# v4_Schematic.net
KiCad netlist of a schematic drawn in Altium Designer
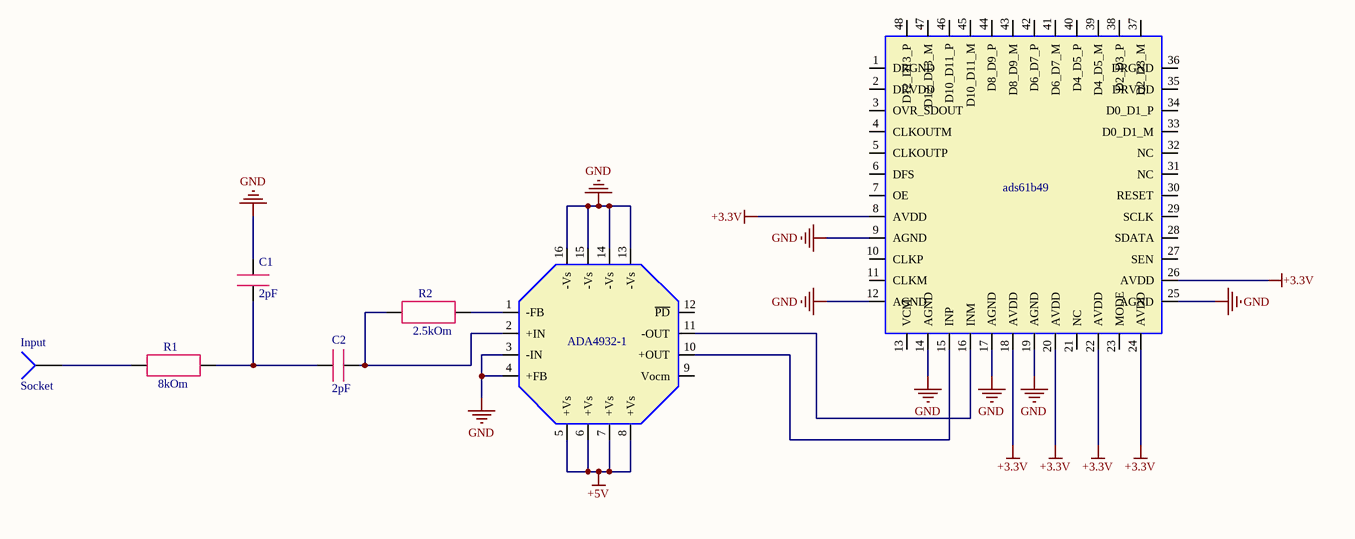
[diagram p0: v4_Schematic.SchDoc]

(export (version "E")
  (design (tool "Eeschema 10.0.6"))
  (components
    (comp (ref "ADA4932-1")
      (value "ADA4932-1")
      (footprint "v4_pcb_librari:ADA4932-1")
      (libsource (lib "v4_librari") (part "ADA4932-1"))
    )
    (comp (ref "ads61b49")
      (value "ads61b49")
      (footprint "v4_pcb_librari:ADS1b49")
      (libsource (lib "v4_librari") (part "ads61b49"))
    )
    (comp (ref "C1")
      (value "2pF")
      (footprint "v4_pcb_librari:C_Capicator")
      (libsource (lib "v4_librari") (part "Ñapacitor"))
    )
    (comp (ref "C2")
      (value "2pF")
      (footprint "v4_pcb_librari:C_Capicator")
      (libsource (lib "v4_librari") (part "Ñapacitor"))
    )
    (comp (ref "Input")
      (value "Socket")
      (footprint "PIN1")
      (fields (field (name "PUBLISHER") "Altium Limited"))
      (libsource (lib "Miscellaneous Connectors") (part "Socket"))
    )
    (comp (ref "R1")
      (value "8kOm")
      (footprint "v4_pcb_librari:R_Resistor")
      (description "8 kOm")
      (libsource (lib "v4_librari") (part "Resistance"))
    )
    (comp (ref "R2")
      (value "2.5kOm")
      (footprint "v4_pcb_librari:R_Resistor")
      (libsource (lib "v4_librari") (part "Resistance"))
    )
  )
  (nets
    (net (code "1") (name "+3.3V") (class "Default")
      (node (ref "ads61b49") (pin "18") (pinfunction "AVDD_18") (pintype "passive"))
      (node (ref "ads61b49") (pin "20") (pinfunction "AVDD_20") (pintype "passive"))
      (node (ref "ads61b49") (pin "22") (pinfunction "AVDD_22") (pintype "passive"))
      (node (ref "ads61b49") (pin "24") (pinfunction "AVDD_24") (pintype "passive"))
      (node (ref "ads61b49") (pin "26") (pinfunction "AVDD_26") (pintype "passive"))
      (node (ref "ads61b49") (pin "8") (pinfunction "AVDD_8") (pintype "passive"))
    )
    (net (code "2") (name "+5V") (class "Default")
      (node (ref "ADA4932-1") (pin "5") (pinfunction "+Vs_5") (pintype "passive"))
      (node (ref "ADA4932-1") (pin "6") (pinfunction "+Vs_6") (pintype "passive"))
      (node (ref "ADA4932-1") (pin "7") (pinfunction "+Vs_7") (pintype "passive"))
      (node (ref "ADA4932-1") (pin "8") (pinfunction "+Vs_8") (pintype "passive"))
    )
    (net (code "3") (name "GND") (class "Default")
      (node (ref "ADA4932-1") (pin "13") (pinfunction "-Vs_13") (pintype "passive"))
      (node (ref "ADA4932-1") (pin "14") (pinfunction "-Vs_14") (pintype "passive"))
      (node (ref "ADA4932-1") (pin "15") (pinfunction "-Vs_15") (pintype "passive"))
      (node (ref "ADA4932-1") (pin "16") (pinfunction "-Vs_16") (pintype "passive"))
      (node (ref "ADA4932-1") (pin "3") (pinfunction "-IN_3") (pintype "passive"))
      (node (ref "ADA4932-1") (pin "4") (pinfunction "+FB_4") (pintype "passive"))
      (node (ref "C1") (pin "2") (pinfunction "2_2") (pintype "passive"))
      (node (ref "ads61b49") (pin "12") (pinfunction "AGND_12") (pintype "passive"))
      (node (ref "ads61b49") (pin "14") (pinfunction "AGND_14") (pintype "passive"))
      (node (ref "ads61b49") (pin "17") (pinfunction "AGND_17") (pintype "passive"))
      (node (ref "ads61b49") (pin "19") (pinfunction "AGND_19") (pintype "passive"))
      (node (ref "ads61b49") (pin "25") (pinfunction "AGND_25") (pintype "passive"))
      (node (ref "ads61b49") (pin "9") (pinfunction "AGND_9") (pintype "passive"))
    )
    (net (code "4") (name "Net-(ADA4932-1-+IN)") (class "Default")
      (node (ref "ADA4932-1") (pin "2") (pinfunction "+IN_2") (pintype "passive"))
      (node (ref "C2") (pin "2") (pinfunction "2_2") (pintype "passive"))
      (node (ref "R2") (pin "1") (pinfunction "1_1") (pintype "passive"))
    )
    (net (code "5") (name "Net-(ADA4932-1-+OUT)") (class "Default")
      (node (ref "ADA4932-1") (pin "10") (pinfunction "+OUT_10") (pintype "passive"))
      (node (ref "ads61b49") (pin "15") (pinfunction "INP_15") (pintype "passive"))
    )
    (net (code "6") (name "Net-(ADA4932-1--FB)") (class "Default")
      (node (ref "ADA4932-1") (pin "1") (pinfunction "-FB_1") (pintype "passive"))
      (node (ref "R2") (pin "2") (pinfunction "2_2") (pintype "passive"))
    )
    (net (code "7") (name "Net-(ADA4932-1--OUT)") (class "Default")
      (node (ref "ADA4932-1") (pin "11") (pinfunction "-OUT_11") (pintype "passive"))
      (node (ref "ads61b49") (pin "16") (pinfunction "INM_16") (pintype "passive"))
    )
    (net (code "8") (name "Net-(C1-Pad1)") (class "Default")
      (node (ref "C1") (pin "1") (pinfunction "1_1") (pintype "passive"))
      (node (ref "C2") (pin "1") (pinfunction "1_1") (pintype "passive"))
      (node (ref "R1") (pin "2") (pinfunction "2_2") (pintype "passive"))
    )
    (net (code "9") (name "Net-(Input-Pad1)") (class "Default")
      (node (ref "Input") (pin "1") (pinfunction "1_1") (pintype "passive"))
      (node (ref "R1") (pin "1") (pinfunction "1_1") (pintype "passive"))
    )
    (net (code "10") (name "unconnected-(ADA4932-1-Vocm-Pad9)") (class "Default")
      (node (ref "ADA4932-1") (pin "9") (pinfunction "Vocm_9") (pintype "passive"))
    )
    (net (code "11") (name "unconnected-(ADA4932-1-~{PD}-Pad12)") (class "Default")
      (node (ref "ADA4932-1") (pin "12") (pinfunction "~{PD}_12") (pintype "passive"))
    )
    (net (code "12") (name "unconnected-(ads61b49-CLKM-Pad11)") (class "Default")
      (node (ref "ads61b49") (pin "11") (pinfunction "CLKM_11") (pintype "passive"))
    )
    (net (code "13") (name "unconnected-(ads61b49-CLKOUTM-Pad4)") (class "Default")
      (node (ref "ads61b49") (pin "4") (pinfunction "CLKOUTM_4") (pintype "passive"))
    )
    (net (code "14") (name "unconnected-(ads61b49-CLKOUTP-Pad5)") (class "Default")
      (node (ref "ads61b49") (pin "5") (pinfunction "CLKOUTP_5") (pintype "passive"))
    )
    (net (code "15") (name "unconnected-(ads61b49-CLKP-Pad10)") (class "Default")
      (node (ref "ads61b49") (pin "10") (pinfunction "CLKP_10") (pintype "passive"))
    )
    (net (code "16") (name "unconnected-(ads61b49-D0_D1_M-Pad33)") (class "Default")
      (node (ref "ads61b49") (pin "33") (pinfunction "D0_D1_M_33") (pintype "passive"))
    )
    (net (code "17") (name "unconnected-(ads61b49-D0_D1_P-Pad34)") (class "Default")
      (node (ref "ads61b49") (pin "34") (pinfunction "D0_D1_P_34") (pintype "passive"))
    )
    (net (code "18") (name "unconnected-(ads61b49-D2_D3_M-Pad37)") (class "Default")
      (node (ref "ads61b49") (pin "37") (pinfunction "D2_D3_M_37") (pintype "passive"))
    )
    (net (code "19") (name "unconnected-(ads61b49-D2_D3_P-Pad38)") (class "Default")
      (node (ref "ads61b49") (pin "38") (pinfunction "D2_D3_P_38") (pintype "passive"))
    )
    (net (code "20") (name "unconnected-(ads61b49-D4_D5_M-Pad39)") (class "Default")
      (node (ref "ads61b49") (pin "39") (pinfunction "D4_D5_M_39") (pintype "passive"))
    )
    (net (code "21") (name "unconnected-(ads61b49-D4_D5_P-Pad40)") (class "Default")
      (node (ref "ads61b49") (pin "40") (pinfunction "D4_D5_P_40") (pintype "passive"))
    )
    (net (code "22") (name "unconnected-(ads61b49-D6_D7_M-Pad41)") (class "Default")
      (node (ref "ads61b49") (pin "41") (pinfunction "D6_D7_M_41") (pintype "passive"))
    )
    (net (code "23") (name "unconnected-(ads61b49-D6_D7_P-Pad42)") (class "Default")
      (node (ref "ads61b49") (pin "42") (pinfunction "D6_D7_P_42") (pintype "passive"))
    )
    (net (code "24") (name "unconnected-(ads61b49-D8_D9_M-Pad43)") (class "Default")
      (node (ref "ads61b49") (pin "43") (pinfunction "D8_D9_M_43") (pintype "passive"))
    )
    (net (code "25") (name "unconnected-(ads61b49-D8_D9_P-Pad44)") (class "Default")
      (node (ref "ads61b49") (pin "44") (pinfunction "D8_D9_P_44") (pintype "passive"))
    )
    (net (code "26") (name "unconnected-(ads61b49-D10_D11_M-Pad45)") (class "Default")
      (node (ref "ads61b49") (pin "45") (pinfunction "D10_D11_M_45") (pintype "passive"))
    )
    (net (code "27") (name "unconnected-(ads61b49-D10_D11_P-Pad46)") (class "Default")
      (node (ref "ads61b49") (pin "46") (pinfunction "D10_D11_P_46") (pintype "passive"))
    )
    (net (code "28") (name "unconnected-(ads61b49-D12_D13_M-Pad47)") (class "Default")
      (node (ref "ads61b49") (pin "47") (pinfunction "D12_D13_M_47") (pintype "passive"))
    )
    (net (code "29") (name "unconnected-(ads61b49-D12_D13_P-Pad48)") (class "Default")
      (node (ref "ads61b49") (pin "48") (pinfunction "D12_D13_P_48") (pintype "passive"))
    )
    (net (code "30") (name "unconnected-(ads61b49-DFS-Pad6)") (class "Default")
      (node (ref "ads61b49") (pin "6") (pinfunction "DFS_6") (pintype "passive"))
    )
    (net (code "31") (name "unconnected-(ads61b49-DRGND-Pad1)") (class "Default")
      (node (ref "ads61b49") (pin "1") (pinfunction "DRGND_1") (pintype "passive"))
    )
    (net (code "32") (name "unconnected-(ads61b49-DRGND-Pad36)") (class "Default")
      (node (ref "ads61b49") (pin "36") (pinfunction "DRGND_36") (pintype "passive"))
    )
    (net (code "33") (name "unconnected-(ads61b49-DRVDD-Pad2)") (class "Default")
      (node (ref "ads61b49") (pin "2") (pinfunction "DRVDD_2") (pintype "passive"))
    )
    (net (code "34") (name "unconnected-(ads61b49-DRVDD-Pad35)") (class "Default")
      (node (ref "ads61b49") (pin "35") (pinfunction "DRVDD_35") (pintype "passive"))
    )
    (net (code "35") (name "unconnected-(ads61b49-MODE-Pad23)") (class "Default")
      (node (ref "ads61b49") (pin "23") (pinfunction "MODE_23") (pintype "passive"))
    )
    (net (code "36") (name "unconnected-(ads61b49-NC-Pad21)") (class "Default")
      (node (ref "ads61b49") (pin "21") (pinfunction "NC_21") (pintype "passive"))
    )
    (net (code "37") (name "unconnected-(ads61b49-NC-Pad31)") (class "Default")
      (node (ref "ads61b49") (pin "31") (pinfunction "NC_31") (pintype "passive"))
    )
    (net (code "38") (name "unconnected-(ads61b49-NC-Pad32)") (class "Default")
      (node (ref "ads61b49") (pin "32") (pinfunction "NC_32") (pintype "passive"))
    )
    (net (code "39") (name "unconnected-(ads61b49-OE-Pad7)") (class "Default")
      (node (ref "ads61b49") (pin "7") (pinfunction "OE_7") (pintype "passive"))
    )
    (net (code "40") (name "unconnected-(ads61b49-OVR_SDOUT-Pad3)") (class "Default")
      (node (ref "ads61b49") (pin "3") (pinfunction "OVR_SDOUT_3") (pintype "passive"))
    )
    (net (code "41") (name "unconnected-(ads61b49-RESET-Pad30)") (class "Default")
      (node (ref "ads61b49") (pin "30") (pinfunction "RESET_30") (pintype "passive"))
    )
    (net (code "42") (name "unconnected-(ads61b49-SCLK-Pad29)") (class "Default")
      (node (ref "ads61b49") (pin "29") (pinfunction "SCLK_29") (pintype "passive"))
    )
    (net (code "43") (name "unconnected-(ads61b49-SDATA-Pad28)") (class "Default")
      (node (ref "ads61b49") (pin "28") (pinfunction "SDATA_28") (pintype "passive"))
    )
    (net (code "44") (name "unconnected-(ads61b49-SEN-Pad27)") (class "Default")
      (node (ref "ads61b49") (pin "27") (pinfunction "SEN_27") (pintype "passive"))
    )
    (net (code "45") (name "unconnected-(ads61b49-VCM-Pad13)") (class "Default")
      (node (ref "ads61b49") (pin "13") (pinfunction "VCM_13") (pintype "passive"))
    )
  )
)
